# Lab4_Sheet1.net
KiCad netlist of a schematic drawn in Altium Designer
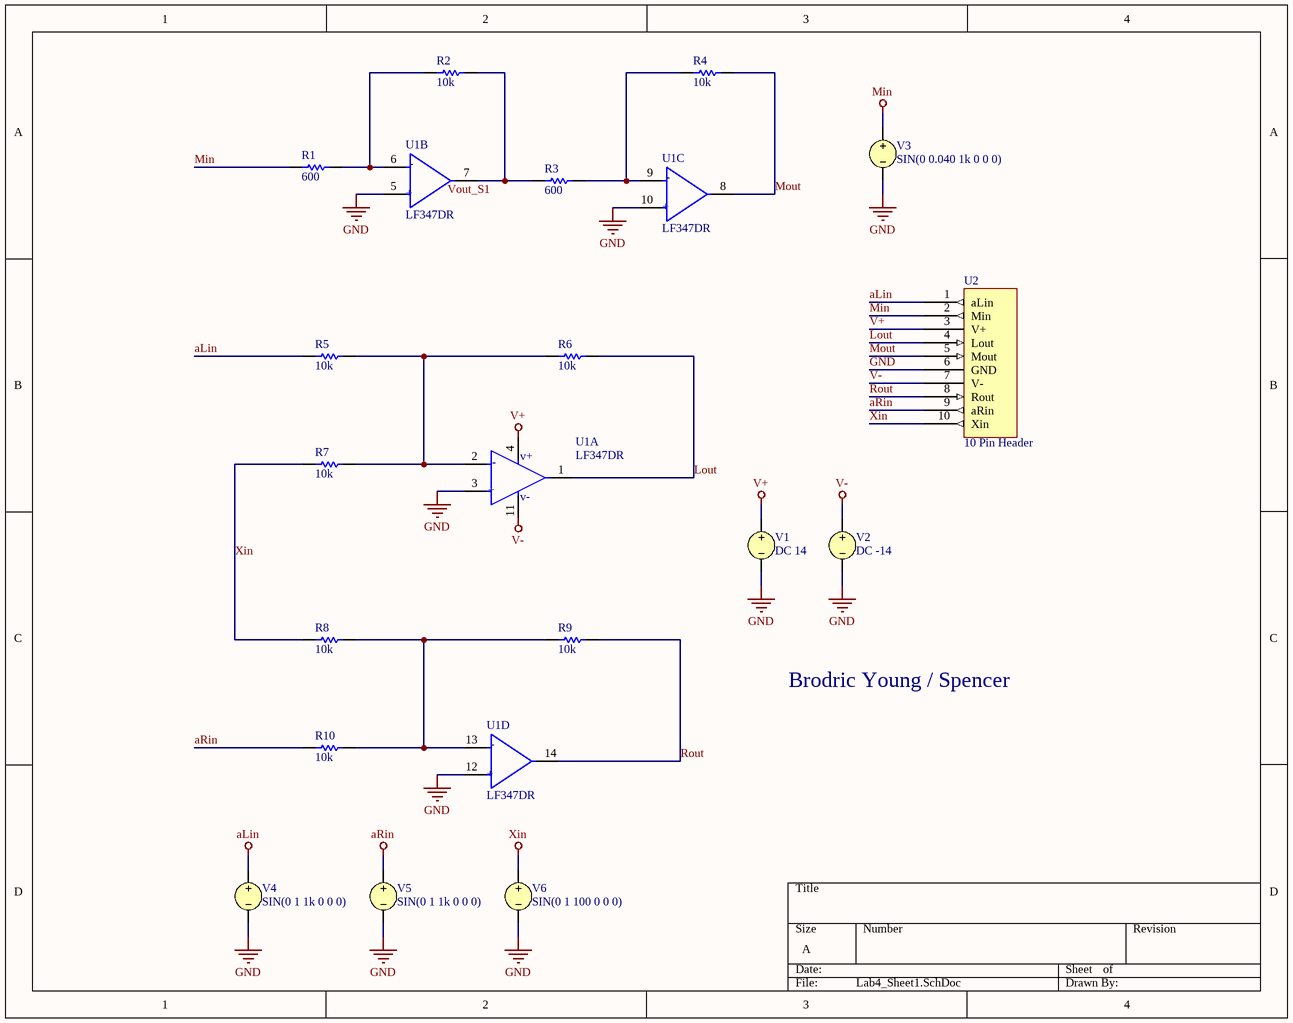
[diagram p0: Lab4_Sheet1.SchDoc]

(export (version "E")
  (design (tool "Eeschema 10.0.6"))
  (components
    (comp (ref "R1")
      (value "600")
      (footprint "KBS_SMD0805")
      (description "Fixed Resistor, 0.25W, 10000ohm, 200V, Surface Mount, 1206")
      (fields (field (name "TOLERANCE") "1%") (field (name "POWER") "250mW"))
      (libsource (lib "ECEN299_Library") (part "CMP-009-00177-1"))
    )
    (comp (ref "R2")
      (value "10k")
      (footprint "KBS_SMD1206")
      (description "Fixed Resistor, 0.25W, 10000ohm, 200V, Surface Mount, 1206")
      (fields (field (name "TOLERANCE") "1%") (field (name "POWER") "250mW"))
      (libsource (lib "ECEN299_Library") (part "CMP-009-00177-1"))
    )
    (comp (ref "R3")
      (value "600")
      (footprint "KBS_SMD0805")
      (description "Fixed Resistor, 0.25W, 10000ohm, 200V, Surface Mount, 1206")
      (fields (field (name "TOLERANCE") "1%") (field (name "POWER") "250mW"))
      (libsource (lib "ECEN299_Library") (part "CMP-009-00177-1"))
    )
    (comp (ref "R4")
      (value "10k")
      (footprint "KBS_SMD1206")
      (description "Fixed Resistor, 0.25W, 10000ohm, 200V, Surface Mount, 1206")
      (fields (field (name "TOLERANCE") "1%") (field (name "POWER") "250mW"))
      (libsource (lib "ECEN299_Library") (part "CMP-009-00177-1"))
    )
    (comp (ref "R5")
      (value "10k")
      (footprint "KBS_SMD1206")
      (description "Fixed Resistor, 0.25W, 10000ohm, 200V, Surface Mount, 1206")
      (fields (field (name "TOLERANCE") "1%") (field (name "POWER") "250mW"))
      (libsource (lib "ECEN299_Library") (part "CMP-009-00177-1"))
    )
    (comp (ref "R6")
      (value "10k")
      (footprint "KBS_SMD1206")
      (description "Fixed Resistor, 0.25W, 10000ohm, 200V, Surface Mount, 1206")
      (fields (field (name "TOLERANCE") "1%") (field (name "POWER") "250mW"))
      (libsource (lib "ECEN299_Library") (part "CMP-009-00177-1"))
    )
    (comp (ref "R7")
      (value "10k")
      (footprint "KBS_SMD1206")
      (description "Fixed Resistor, 0.25W, 10000ohm, 200V, Surface Mount, 1206")
      (fields (field (name "TOLERANCE") "1%") (field (name "POWER") "250mW"))
      (libsource (lib "ECEN299_Library") (part "CMP-009-00177-1"))
    )
    (comp (ref "R8")
      (value "10k")
      (footprint "KBS_SMD1206")
      (description "Fixed Resistor, 0.25W, 10000ohm, 200V, Surface Mount, 1206")
      (fields (field (name "TOLERANCE") "1%") (field (name "POWER") "250mW"))
      (libsource (lib "ECEN299_Library") (part "CMP-009-00177-1"))
    )
    (comp (ref "R9")
      (value "10k")
      (footprint "KBS_SMD1206")
      (description "Fixed Resistor, 0.25W, 10000ohm, 200V, Surface Mount, 1206")
      (fields (field (name "TOLERANCE") "1%") (field (name "POWER") "250mW"))
      (libsource (lib "ECEN299_Library") (part "CMP-009-00177-1"))
    )
    (comp (ref "R10")
      (value "10k")
      (footprint "KBS_SMD1206")
      (description "Fixed Resistor, 0.25W, 10000ohm, 200V, Surface Mount, 1206")
      (fields (field (name "TOLERANCE") "1%") (field (name "POWER") "250mW"))
      (libsource (lib "ECEN299_Library") (part "CMP-009-00177-1"))
    )
    (comp (ref "U1")
      (value "LF347DR")
      (footprint "KBS_SO14_w_Guide_Pin_Holes")
      (description "Operational Amplifier, 4 Func, 13000uV Offset-Max, JFET, PDSO14")
      (fields (field (name "MANUFACTURER") "Texas Instruments"))
      (libsource (lib "ECEN299_Library") (part "CMP-014-00002-1"))
    )
    (comp (ref "U2")
      (value "10 Pin Header")
      (footprint "KBS_10pin_Header_PreA_Mixer")
      (libsource (lib "ECEN299_Library") (part "10 Pin Header"))
    )
    (comp (ref "V1")
      (value "DC 14")
      (description "Voltage Source")
      (fields (field (name "PUBLISHER") "Altium Limited"))
      (libsource (lib "Simulation Generic Components") (part "VSRC"))
    )
    (comp (ref "V2")
      (value "DC -14")
      (description "Voltage Source")
      (fields (field (name "PUBLISHER") "Altium Limited"))
      (libsource (lib "Simulation Generic Components") (part "VSRC"))
    )
    (comp (ref "V3")
      (value "SIN(0 0.040 1k 0 0 0)")
      (description "Voltage Source")
      (fields (field (name "PUBLISHER") "Altium Limited"))
      (libsource (lib "Simulation Generic Components") (part "VSRC"))
    )
    (comp (ref "V4")
      (value "SIN(0 1 1k 0 0 0)")
      (description "Voltage Source")
      (fields (field (name "PUBLISHER") "Altium Limited"))
      (libsource (lib "Simulation Generic Components") (part "VSRC"))
    )
    (comp (ref "V5")
      (value "SIN(0 1 1k 0 0 0)")
      (description "Voltage Source")
      (fields (field (name "PUBLISHER") "Altium Limited"))
      (libsource (lib "Simulation Generic Components") (part "VSRC"))
    )
    (comp (ref "V6")
      (value "SIN(0 1 100 0 0 0)")
      (description "Voltage Source")
      (fields (field (name "PUBLISHER") "Altium Limited"))
      (libsource (lib "Simulation Generic Components") (part "VSRC"))
    )
  )
  (nets
    (net (code "1") (name "/Lout") (class "Default")
      (node (ref "R6") (pin "2") (pinfunction "2_2") (pintype "passive"))
      (node (ref "U1") (pin "1") (pinfunction "1OUT_1") (pintype "passive"))
      (node (ref "U2") (pin "4") (pinfunction "Lout_4") (pintype "input"))
    )
    (net (code "2") (name "/Mout") (class "Default")
      (node (ref "R4") (pin "2") (pinfunction "2_2") (pintype "passive"))
      (node (ref "U1") (pin "8") (pinfunction "3OUT_8") (pintype "passive"))
      (node (ref "U2") (pin "5") (pinfunction "Mout_5") (pintype "input"))
    )
    (net (code "3") (name "/Rout") (class "Default")
      (node (ref "R9") (pin "2") (pinfunction "2_2") (pintype "passive"))
      (node (ref "U1") (pin "14") (pinfunction "4OUT_14") (pintype "passive"))
      (node (ref "U2") (pin "8") (pinfunction "Rout_8") (pintype "input"))
    )
    (net (code "4") (name "/Vout_S1") (class "Default")
      (node (ref "R2") (pin "2") (pinfunction "2_2") (pintype "passive"))
      (node (ref "R3") (pin "1") (pinfunction "1_1") (pintype "passive"))
      (node (ref "U1") (pin "7") (pinfunction "2OUT_7") (pintype "passive"))
    )
    (net (code "5") (name "GND") (class "Default")
      (node (ref "U1") (pin "10") (pinfunction "3IN+_10") (pintype "tri_state"))
      (node (ref "U1") (pin "12") (pinfunction "4IN+_12") (pintype "tri_state"))
      (node (ref "U1") (pin "3") (pinfunction "1IN+_3") (pintype "tri_state"))
      (node (ref "U1") (pin "5") (pinfunction "2IN+_5") (pintype "tri_state"))
      (node (ref "U2") (pin "6") (pinfunction "GND_6") (pintype "power_in"))
      (node (ref "V1") (pin "2") (pinfunction "2_2") (pintype "passive"))
      (node (ref "V2") (pin "2") (pinfunction "2_2") (pintype "passive"))
      (node (ref "V3") (pin "2") (pinfunction "2_2") (pintype "passive"))
      (node (ref "V4") (pin "2") (pinfunction "2_2") (pintype "passive"))
      (node (ref "V5") (pin "2") (pinfunction "2_2") (pintype "passive"))
      (node (ref "V6") (pin "2") (pinfunction "2_2") (pintype "passive"))
    )
    (net (code "6") (name "Min") (class "Default")
      (node (ref "R1") (pin "1") (pinfunction "1_1") (pintype "passive"))
      (node (ref "U2") (pin "2") (pinfunction "Min_2") (pintype "output"))
      (node (ref "V3") (pin "1") (pinfunction "1_1") (pintype "passive"))
    )
    (net (code "7") (name "Net-(U1A-1IN-)") (class "Default")
      (node (ref "R5") (pin "2") (pinfunction "2_2") (pintype "passive"))
      (node (ref "R6") (pin "1") (pinfunction "1_1") (pintype "passive"))
      (node (ref "R7") (pin "2") (pinfunction "2_2") (pintype "passive"))
      (node (ref "U1") (pin "2") (pinfunction "1IN-_2") (pintype "tri_state"))
    )
    (net (code "8") (name "Net-(U1B-2IN-)") (class "Default")
      (node (ref "R1") (pin "2") (pinfunction "2_2") (pintype "passive"))
      (node (ref "R2") (pin "1") (pinfunction "1_1") (pintype "passive"))
      (node (ref "U1") (pin "6") (pinfunction "2IN-_6") (pintype "tri_state"))
    )
    (net (code "9") (name "Net-(U1C-3IN-)") (class "Default")
      (node (ref "R3") (pin "2") (pinfunction "2_2") (pintype "passive"))
      (node (ref "R4") (pin "1") (pinfunction "1_1") (pintype "passive"))
      (node (ref "U1") (pin "9") (pinfunction "3IN-_9") (pintype "tri_state"))
    )
    (net (code "10") (name "Net-(U1D-4IN-)") (class "Default")
      (node (ref "R10") (pin "2") (pinfunction "2_2") (pintype "passive"))
      (node (ref "R8") (pin "2") (pinfunction "2_2") (pintype "passive"))
      (node (ref "R9") (pin "1") (pinfunction "1_1") (pintype "passive"))
      (node (ref "U1") (pin "13") (pinfunction "4IN-_13") (pintype "tri_state"))
    )
    (net (code "11") (name "V+") (class "Default")
      (node (ref "U1") (pin "4") (pinfunction "VCC+_4") (pintype "power_in"))
      (node (ref "U2") (pin "3") (pinfunction "V+_3") (pintype "power_in"))
      (node (ref "V1") (pin "1") (pinfunction "1_1") (pintype "passive"))
    )
    (net (code "12") (name "V-") (class "Default")
      (node (ref "U1") (pin "11") (pinfunction "VCC-_11") (pintype "power_in"))
      (node (ref "U2") (pin "7") (pinfunction "V-_7") (pintype "power_in"))
      (node (ref "V2") (pin "1") (pinfunction "1_1") (pintype "passive"))
    )
    (net (code "13") (name "Xin") (class "Default")
      (node (ref "R7") (pin "1") (pinfunction "1_1") (pintype "passive"))
      (node (ref "R8") (pin "1") (pinfunction "1_1") (pintype "passive"))
      (node (ref "U2") (pin "10") (pinfunction "Xin_10") (pintype "output"))
      (node (ref "V6") (pin "1") (pinfunction "1_1") (pintype "passive"))
    )
    (net (code "14") (name "aLin") (class "Default")
      (node (ref "R5") (pin "1") (pinfunction "1_1") (pintype "passive"))
      (node (ref "U2") (pin "1") (pinfunction "aLin_1") (pintype "output"))
      (node (ref "V4") (pin "1") (pinfunction "1_1") (pintype "passive"))
    )
    (net (code "15") (name "aRin") (class "Default")
      (node (ref "R10") (pin "1") (pinfunction "1_1") (pintype "passive"))
      (node (ref "U2") (pin "9") (pinfunction "aRin_9") (pintype "output"))
      (node (ref "V5") (pin "1") (pinfunction "1_1") (pintype "passive"))
    )
  )
)
